# BL653u.net
KiCad netlist of a schematic drawn in Altium Designer
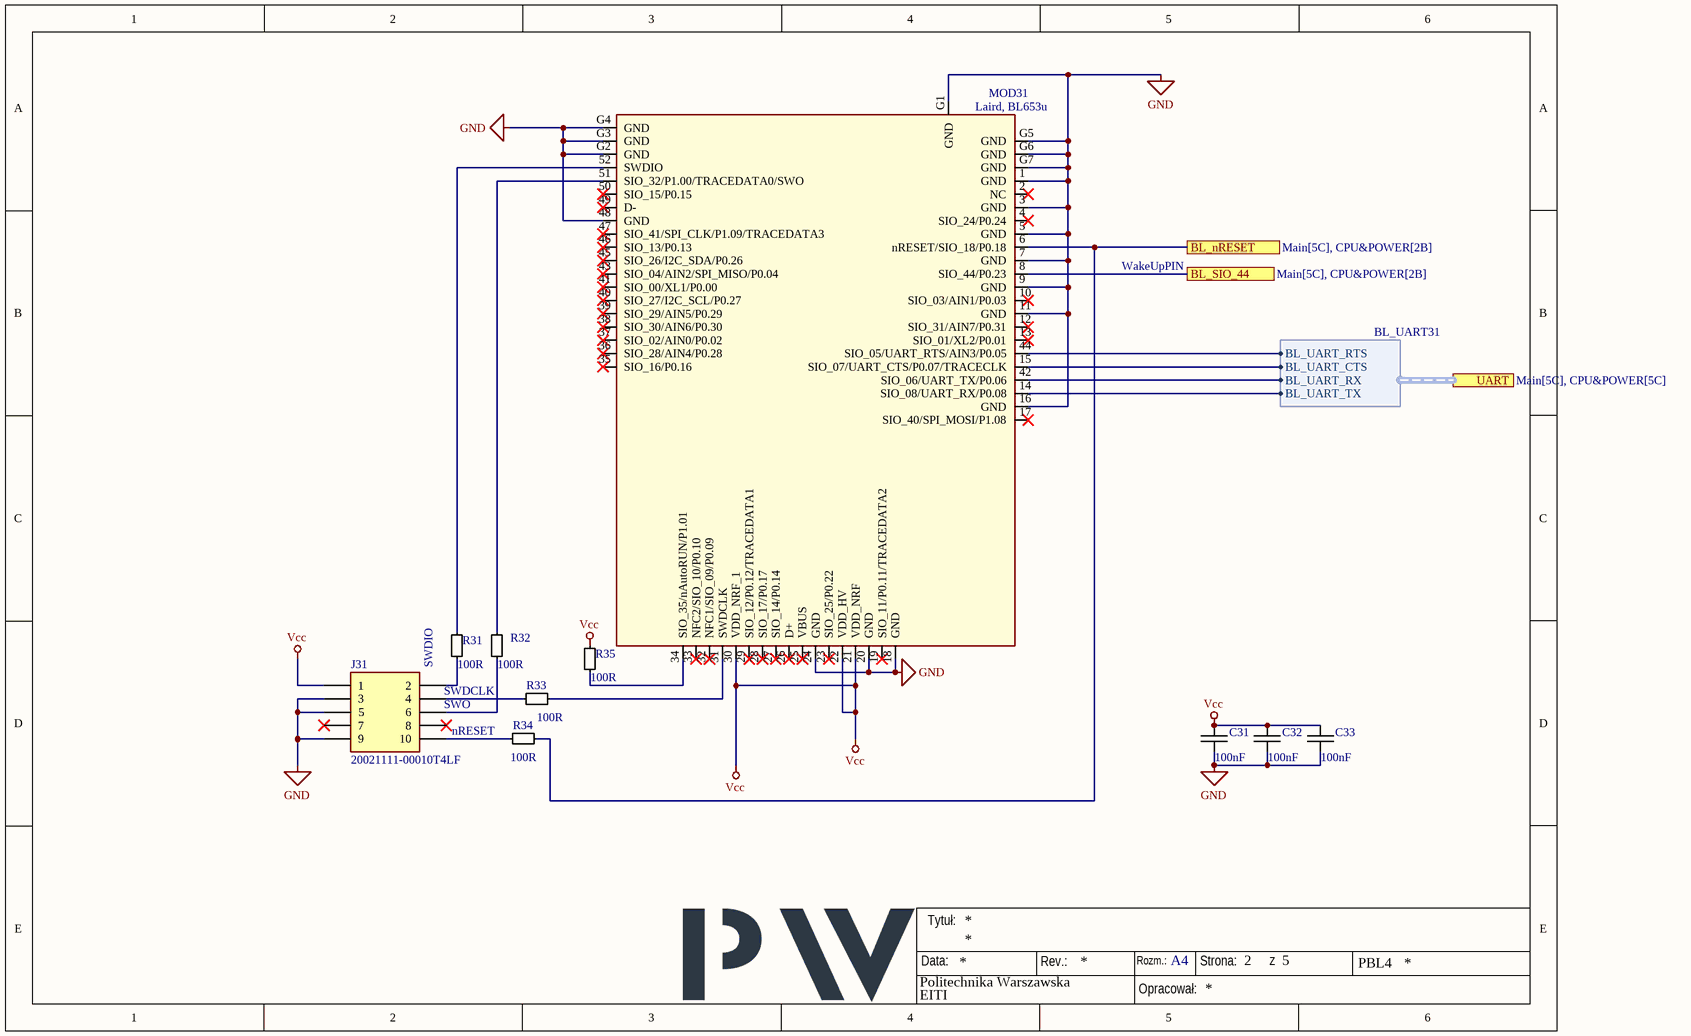
[diagram p0: BL653u.SchDoc]

(export (version "E")
  (design (tool "Eeschema 10.0.6"))
  (components
    (comp (ref "C31")
      (value "100nF")
      (footprint "0402_CAP")
      (description "Ceramic Capacitor")
      (fields (field (name "PARAMETER 1") "100nF"))
      (libsource (lib "Zad1") (part "Capacitor_1"))
    )
    (comp (ref "C32")
      (value "100nF")
      (footprint "0402_CAP")
      (description "Ceramic Capacitor")
      (fields (field (name "PARAMETER 1") "100nF"))
      (libsource (lib "Zad1") (part "Capacitor_1"))
    )
    (comp (ref "C33")
      (value "100nF")
      (footprint "0402_CAP")
      (description "Ceramic Capacitor")
      (fields (field (name "PARAMETER 1") "100nF"))
      (libsource (lib "Zad1") (part "Capacitor_1"))
    )
    (comp (ref "J31")
      (value "20021111-00010T4LF")
      (footprint "HDRV10W41P127_2X5_635X343X575P_m")
      (description "Connector")
      (fields (field (name "MOUSER PART NUMBER") "649-221111-00010T4LF"))
      (libsource (lib "SamacSys") (part "20021111-00010T4LF"))
    )
    (comp (ref "MOD31")
      (value "Laird, BL653u")
      (footprint "45300059C_m")
      (description "BL653µ Integrated Antenna module, 453-00059")
      (fields (field (name "MANUFACTURER PART NUMBER") "453-00059") (field (name "MANUFACTURER") "Laird"))
      (libsource (lib "BL653u_Integrated Antenna module 453-00059 SCH Symbol") (part "Laird, BL653u"))
    )
    (comp (ref "R31")
      (value "100R")
      (footprint "0402_RES")
      (fields (field (name "PARAMETER 1") "100R"))
      (libsource (lib "") (part "Resistor_2"))
    )
    (comp (ref "R32")
      (value "100R")
      (footprint "0402_RES")
      (fields (field (name "PARAMETER 1") "100R"))
      (libsource (lib "") (part "Resistor_2"))
    )
    (comp (ref "R33")
      (value "100R")
      (footprint "0402_RES")
      (fields (field (name "PARAMETER 1") "100R"))
      (libsource (lib "Zad1") (part "Resistor"))
    )
    (comp (ref "R34")
      (value "100R")
      (footprint "0402_RES")
      (description "Resistor")
      (fields (field (name "PARAMETER 1") "100R"))
      (libsource (lib "Zad1") (part "Resistor"))
    )
    (comp (ref "R35")
      (value "100R")
      (footprint "0402_RES")
      (fields (field (name "PARAMETER 1") "100R"))
      (libsource (lib "") (part "Resistor_1"))
    )
  )
  (nets
    (net (code "2") (name "/BL_SIO_44") (class "Default")
      (node (ref "MOD31") (pin "8") (pinfunction "SIO_44/P0.23_8") (pintype "passive"))
    )
    (net (code "3") (name "/BL_UART_CTS") (class "Default")
      (node (ref "MOD31") (pin "15") (pinfunction "SIO_07/UART_CTS/P0.07/TRACECLK_15") (pintype "passive"))
    )
    (net (code "4") (name "/BL_UART_RTS") (class "Default")
      (node (ref "MOD31") (pin "44") (pinfunction "SIO_05/UART_RTS/AIN3/P0.05_44") (pintype "passive"))
    )
    (net (code "5") (name "/BL_UART_RX") (class "Default")
      (node (ref "MOD31") (pin "42") (pinfunction "SIO_06/UART_TX/P0.06_42") (pintype "passive"))
    )
    (net (code "6") (name "/BL_UART_TX") (class "Default")
      (node (ref "MOD31") (pin "14") (pinfunction "SIO_08/UART_RX/P0.08_14") (pintype "passive"))
    )
    (net (code "7") (name "/BL_nRESET") (class "Default")
      (node (ref "MOD31") (pin "6") (pinfunction "nRESET/SIO_18/P0.18_6") (pintype "passive"))
      (node (ref "R34") (pin "1") (pinfunction "1_1") (pintype "passive"))
    )
    (net (code "9") (name "GND") (class "Default")
      (node (ref "C31") (pin "2") (pinfunction "0_2") (pintype "passive"))
      (node (ref "C32") (pin "2") (pinfunction "0_2") (pintype "passive"))
      (node (ref "C33") (pin "2") (pinfunction "0_2") (pintype "passive"))
      (node (ref "J31") (pin "3") (pinfunction "3_3") (pintype "passive"))
      (node (ref "J31") (pin "5") (pinfunction "5_5") (pintype "passive"))
      (node (ref "J31") (pin "9") (pinfunction "9_9") (pintype "passive"))
      (node (ref "MOD31") (pin "1") (pinfunction "GND_1") (pintype "passive"))
      (node (ref "MOD31") (pin "11") (pinfunction "GND_11") (pintype "passive"))
      (node (ref "MOD31") (pin "16") (pinfunction "GND_16") (pintype "passive"))
      (node (ref "MOD31") (pin "18") (pinfunction "GND_18") (pintype "passive"))
      (node (ref "MOD31") (pin "20") (pinfunction "GND_20") (pintype "passive"))
      (node (ref "MOD31") (pin "24") (pinfunction "GND_24") (pintype "passive"))
      (node (ref "MOD31") (pin "3") (pinfunction "GND_3") (pintype "passive"))
      (node (ref "MOD31") (pin "48") (pinfunction "GND_48") (pintype "passive"))
      (node (ref "MOD31") (pin "5") (pinfunction "GND_5") (pintype "passive"))
      (node (ref "MOD31") (pin "7") (pinfunction "GND_7") (pintype "passive"))
      (node (ref "MOD31") (pin "9") (pinfunction "GND_9") (pintype "passive"))
      (node (ref "MOD31") (pin "G1") (pinfunction "GND_G1") (pintype "passive"))
      (node (ref "MOD31") (pin "G2") (pinfunction "GND_G2") (pintype "passive"))
      (node (ref "MOD31") (pin "G3") (pinfunction "GND_G3") (pintype "passive"))
      (node (ref "MOD31") (pin "G4") (pinfunction "GND_G4") (pintype "passive"))
      (node (ref "MOD31") (pin "G5") (pinfunction "GND_G5") (pintype "passive"))
      (node (ref "MOD31") (pin "G6") (pinfunction "GND_G6") (pintype "passive"))
      (node (ref "MOD31") (pin "G7") (pinfunction "GND_G7") (pintype "passive"))
    )
    (net (code "10") (name "Net-(J31-Pad2)") (class "Default")
      (node (ref "J31") (pin "2") (pinfunction "2_2") (pintype "passive"))
      (node (ref "R31") (pin "1") (pinfunction "1_1") (pintype "passive"))
    )
    (net (code "11") (name "Net-(J31-Pad4)") (class "Default")
      (node (ref "J31") (pin "4") (pinfunction "4_4") (pintype "passive"))
      (node (ref "R33") (pin "2") (pinfunction "2_2") (pintype "passive"))
    )
    (net (code "12") (name "Net-(J31-Pad6)") (class "Default")
      (node (ref "J31") (pin "6") (pinfunction "6_6") (pintype "passive"))
      (node (ref "R32") (pin "1") (pinfunction "1_1") (pintype "passive"))
    )
    (net (code "13") (name "Net-(J31-Pad10)") (class "Default")
      (node (ref "J31") (pin "10") (pinfunction "10_10") (pintype "passive"))
      (node (ref "R34") (pin "2") (pinfunction "2_2") (pintype "passive"))
    )
    (net (code "14") (name "Net-(MOD31-SIO_32{slash}P1.00{slash}TRACEDATA0{slash}SWO)") (class "Default")
      (node (ref "MOD31") (pin "51") (pinfunction "SIO_32/P1.00/TRACEDATA0/SWO_51") (pintype "passive"))
      (node (ref "R32") (pin "2") (pinfunction "2_2") (pintype "passive"))
    )
    (net (code "15") (name "Net-(MOD31-SIO_35{slash}nAutoRUN{slash}P1.01)") (class "Default")
      (node (ref "MOD31") (pin "34") (pinfunction "SIO_35/nAutoRUN/P1.01_34") (pintype "passive"))
      (node (ref "R35") (pin "2") (pinfunction "2_2") (pintype "passive"))
    )
    (net (code "16") (name "Net-(MOD31-SWDCLK)") (class "Default")
      (node (ref "MOD31") (pin "31") (pinfunction "SWDCLK_31") (pintype "passive"))
      (node (ref "R33") (pin "1") (pinfunction "1_1") (pintype "passive"))
    )
    (net (code "17") (name "Net-(MOD31-SWDIO)") (class "Default")
      (node (ref "MOD31") (pin "52") (pinfunction "SWDIO_52") (pintype "passive"))
      (node (ref "R31") (pin "2") (pinfunction "2_2") (pintype "passive"))
    )
    (net (code "18") (name "Vcc") (class "Default")
      (node (ref "C31") (pin "1") (pinfunction "0_1") (pintype "passive"))
      (node (ref "C32") (pin "1") (pinfunction "0_1") (pintype "passive"))
      (node (ref "C33") (pin "1") (pinfunction "0_1") (pintype "passive"))
      (node (ref "J31") (pin "1") (pinfunction "1_1") (pintype "passive"))
      (node (ref "MOD31") (pin "21") (pinfunction "VDD_NRF_21") (pintype "passive"))
      (node (ref "MOD31") (pin "22") (pinfunction "VDD_HV_22") (pintype "passive"))
      (node (ref "MOD31") (pin "30") (pinfunction "VDD_NRF_1_30") (pintype "passive"))
      (node (ref "R35") (pin "1") (pinfunction "1_1") (pintype "passive"))
    )
    (net (code "19") (name "unconnected-(J31-Pad7)") (class "Default")
      (node (ref "J31") (pin "7") (pinfunction "7_7") (pintype "passive+no_connect"))
    )
    (net (code "20") (name "unconnected-(J31-Pad8)") (class "Default")
      (node (ref "J31") (pin "8") (pinfunction "8_8") (pintype "passive+no_connect"))
    )
    (net (code "21") (name "unconnected-(MOD31-D+-Pad26)") (class "Default")
      (node (ref "MOD31") (pin "26") (pinfunction "D+_26") (pintype "passive+no_connect"))
    )
    (net (code "22") (name "unconnected-(MOD31-D--Pad49)") (class "Default")
      (node (ref "MOD31") (pin "49") (pinfunction "D-_49") (pintype "passive+no_connect"))
    )
    (net (code "23") (name "unconnected-(MOD31-NC-Pad2)") (class "Default")
      (node (ref "MOD31") (pin "2") (pinfunction "NC_2") (pintype "passive+no_connect"))
    )
    (net (code "24") (name "unconnected-(MOD31-NFC1{slash}SIO_09{slash}P0.09-Pad32)") (class "Default")
      (node (ref "MOD31") (pin "32") (pinfunction "NFC1/SIO_09/P0.09_32") (pintype "passive+no_connect"))
    )
    (net (code "25") (name "unconnected-(MOD31-NFC2{slash}SIO_10{slash}P0.10-Pad33)") (class "Default")
      (node (ref "MOD31") (pin "33") (pinfunction "NFC2/SIO_10/P0.10_33") (pintype "passive+no_connect"))
    )
    (net (code "26") (name "unconnected-(MOD31-SIO_00{slash}XL1{slash}P0.00-Pad41)") (class "Default")
      (node (ref "MOD31") (pin "41") (pinfunction "SIO_00/XL1/P0.00_41") (pintype "passive+no_connect"))
    )
    (net (code "27") (name "unconnected-(MOD31-SIO_01{slash}XL2{slash}P0.01-Pad13)") (class "Default")
      (node (ref "MOD31") (pin "13") (pinfunction "SIO_01/XL2/P0.01_13") (pintype "passive+no_connect"))
    )
    (net (code "28") (name "unconnected-(MOD31-SIO_02{slash}AIN0{slash}P0.02-Pad37)") (class "Default")
      (node (ref "MOD31") (pin "37") (pinfunction "SIO_02/AIN0/P0.02_37") (pintype "passive+no_connect"))
    )
    (net (code "29") (name "unconnected-(MOD31-SIO_03{slash}AIN1{slash}P0.03-Pad10)") (class "Default")
      (node (ref "MOD31") (pin "10") (pinfunction "SIO_03/AIN1/P0.03_10") (pintype "passive+no_connect"))
    )
    (net (code "30") (name "unconnected-(MOD31-SIO_04{slash}AIN2{slash}SPI_MISO{slash}P0.04-Pad43)") (class "Default")
      (node (ref "MOD31") (pin "43") (pinfunction "SIO_04/AIN2/SPI_MISO/P0.04_43") (pintype "passive+no_connect"))
    )
    (net (code "31") (name "unconnected-(MOD31-SIO_11{slash}P0.11{slash}TRACEDATA2-Pad19)") (class "Default")
      (node (ref "MOD31") (pin "19") (pinfunction "SIO_11/P0.11/TRACEDATA2_19") (pintype "passive+no_connect"))
    )
    (net (code "32") (name "unconnected-(MOD31-SIO_12{slash}P0.12{slash}TRACEDATA1-Pad29)") (class "Default")
      (node (ref "MOD31") (pin "29") (pinfunction "SIO_12/P0.12/TRACEDATA1_29") (pintype "passive+no_connect"))
    )
    (net (code "33") (name "unconnected-(MOD31-SIO_13{slash}P0.13-Pad46)") (class "Default")
      (node (ref "MOD31") (pin "46") (pinfunction "SIO_13/P0.13_46") (pintype "passive+no_connect"))
    )
    (net (code "34") (name "unconnected-(MOD31-SIO_14{slash}P0.14-Pad27)") (class "Default")
      (node (ref "MOD31") (pin "27") (pinfunction "SIO_14/P0.14_27") (pintype "passive+no_connect"))
    )
    (net (code "35") (name "unconnected-(MOD31-SIO_15{slash}P0.15-Pad50)") (class "Default")
      (node (ref "MOD31") (pin "50") (pinfunction "SIO_15/P0.15_50") (pintype "passive+no_connect"))
    )
    (net (code "36") (name "unconnected-(MOD31-SIO_16{slash}P0.16-Pad35)") (class "Default")
      (node (ref "MOD31") (pin "35") (pinfunction "SIO_16/P0.16_35") (pintype "passive+no_connect"))
    )
    (net (code "37") (name "unconnected-(MOD31-SIO_17{slash}P0.17-Pad28)") (class "Default")
      (node (ref "MOD31") (pin "28") (pinfunction "SIO_17/P0.17_28") (pintype "passive+no_connect"))
    )
    (net (code "38") (name "unconnected-(MOD31-SIO_24{slash}P0.24-Pad4)") (class "Default")
      (node (ref "MOD31") (pin "4") (pinfunction "SIO_24/P0.24_4") (pintype "passive+no_connect"))
    )
    (net (code "39") (name "unconnected-(MOD31-SIO_25{slash}P0.22-Pad23)") (class "Default")
      (node (ref "MOD31") (pin "23") (pinfunction "SIO_25/P0.22_23") (pintype "passive+no_connect"))
    )
    (net (code "40") (name "unconnected-(MOD31-SIO_26{slash}I2C_SDA{slash}P0.26-Pad45)") (class "Default")
      (node (ref "MOD31") (pin "45") (pinfunction "SIO_26/I2C_SDA/P0.26_45") (pintype "passive+no_connect"))
    )
    (net (code "41") (name "unconnected-(MOD31-SIO_27{slash}I2C_SCL{slash}P0.27-Pad40)") (class "Default")
      (node (ref "MOD31") (pin "40") (pinfunction "SIO_27/I2C_SCL/P0.27_40") (pintype "passive+no_connect"))
    )
    (net (code "42") (name "unconnected-(MOD31-SIO_28{slash}AIN4{slash}P0.28-Pad36)") (class "Default")
      (node (ref "MOD31") (pin "36") (pinfunction "SIO_28/AIN4/P0.28_36") (pintype "passive+no_connect"))
    )
    (net (code "43") (name "unconnected-(MOD31-SIO_29{slash}AIN5{slash}P0.29-Pad39)") (class "Default")
      (node (ref "MOD31") (pin "39") (pinfunction "SIO_29/AIN5/P0.29_39") (pintype "passive+no_connect"))
    )
    (net (code "44") (name "unconnected-(MOD31-SIO_30{slash}AIN6{slash}P0.30-Pad38)") (class "Default")
      (node (ref "MOD31") (pin "38") (pinfunction "SIO_30/AIN6/P0.30_38") (pintype "passive+no_connect"))
    )
    (net (code "45") (name "unconnected-(MOD31-SIO_31{slash}AIN7{slash}P0.31-Pad12)") (class "Default")
      (node (ref "MOD31") (pin "12") (pinfunction "SIO_31/AIN7/P0.31_12") (pintype "passive+no_connect"))
    )
    (net (code "46") (name "unconnected-(MOD31-SIO_40{slash}SPI_MOSI{slash}P1.08-Pad17)") (class "Default")
      (node (ref "MOD31") (pin "17") (pinfunction "SIO_40/SPI_MOSI/P1.08_17") (pintype "passive+no_connect"))
    )
    (net (code "47") (name "unconnected-(MOD31-SIO_41{slash}SPI_CLK{slash}P1.09{slash}TRACEDATA3-Pad47)") (class "Default")
      (node (ref "MOD31") (pin "47") (pinfunction "SIO_41/SPI_CLK/P1.09/TRACEDATA3_47") (pintype "passive+no_connect"))
    )
    (net (code "48") (name "unconnected-(MOD31-VBUS-Pad25)") (class "Default")
      (node (ref "MOD31") (pin "25") (pinfunction "VBUS_25") (pintype "passive+no_connect"))
    )
  )
)
